# EECS430PhasedArray.net
KiCad netlist of a schematic drawn in Altium Designer
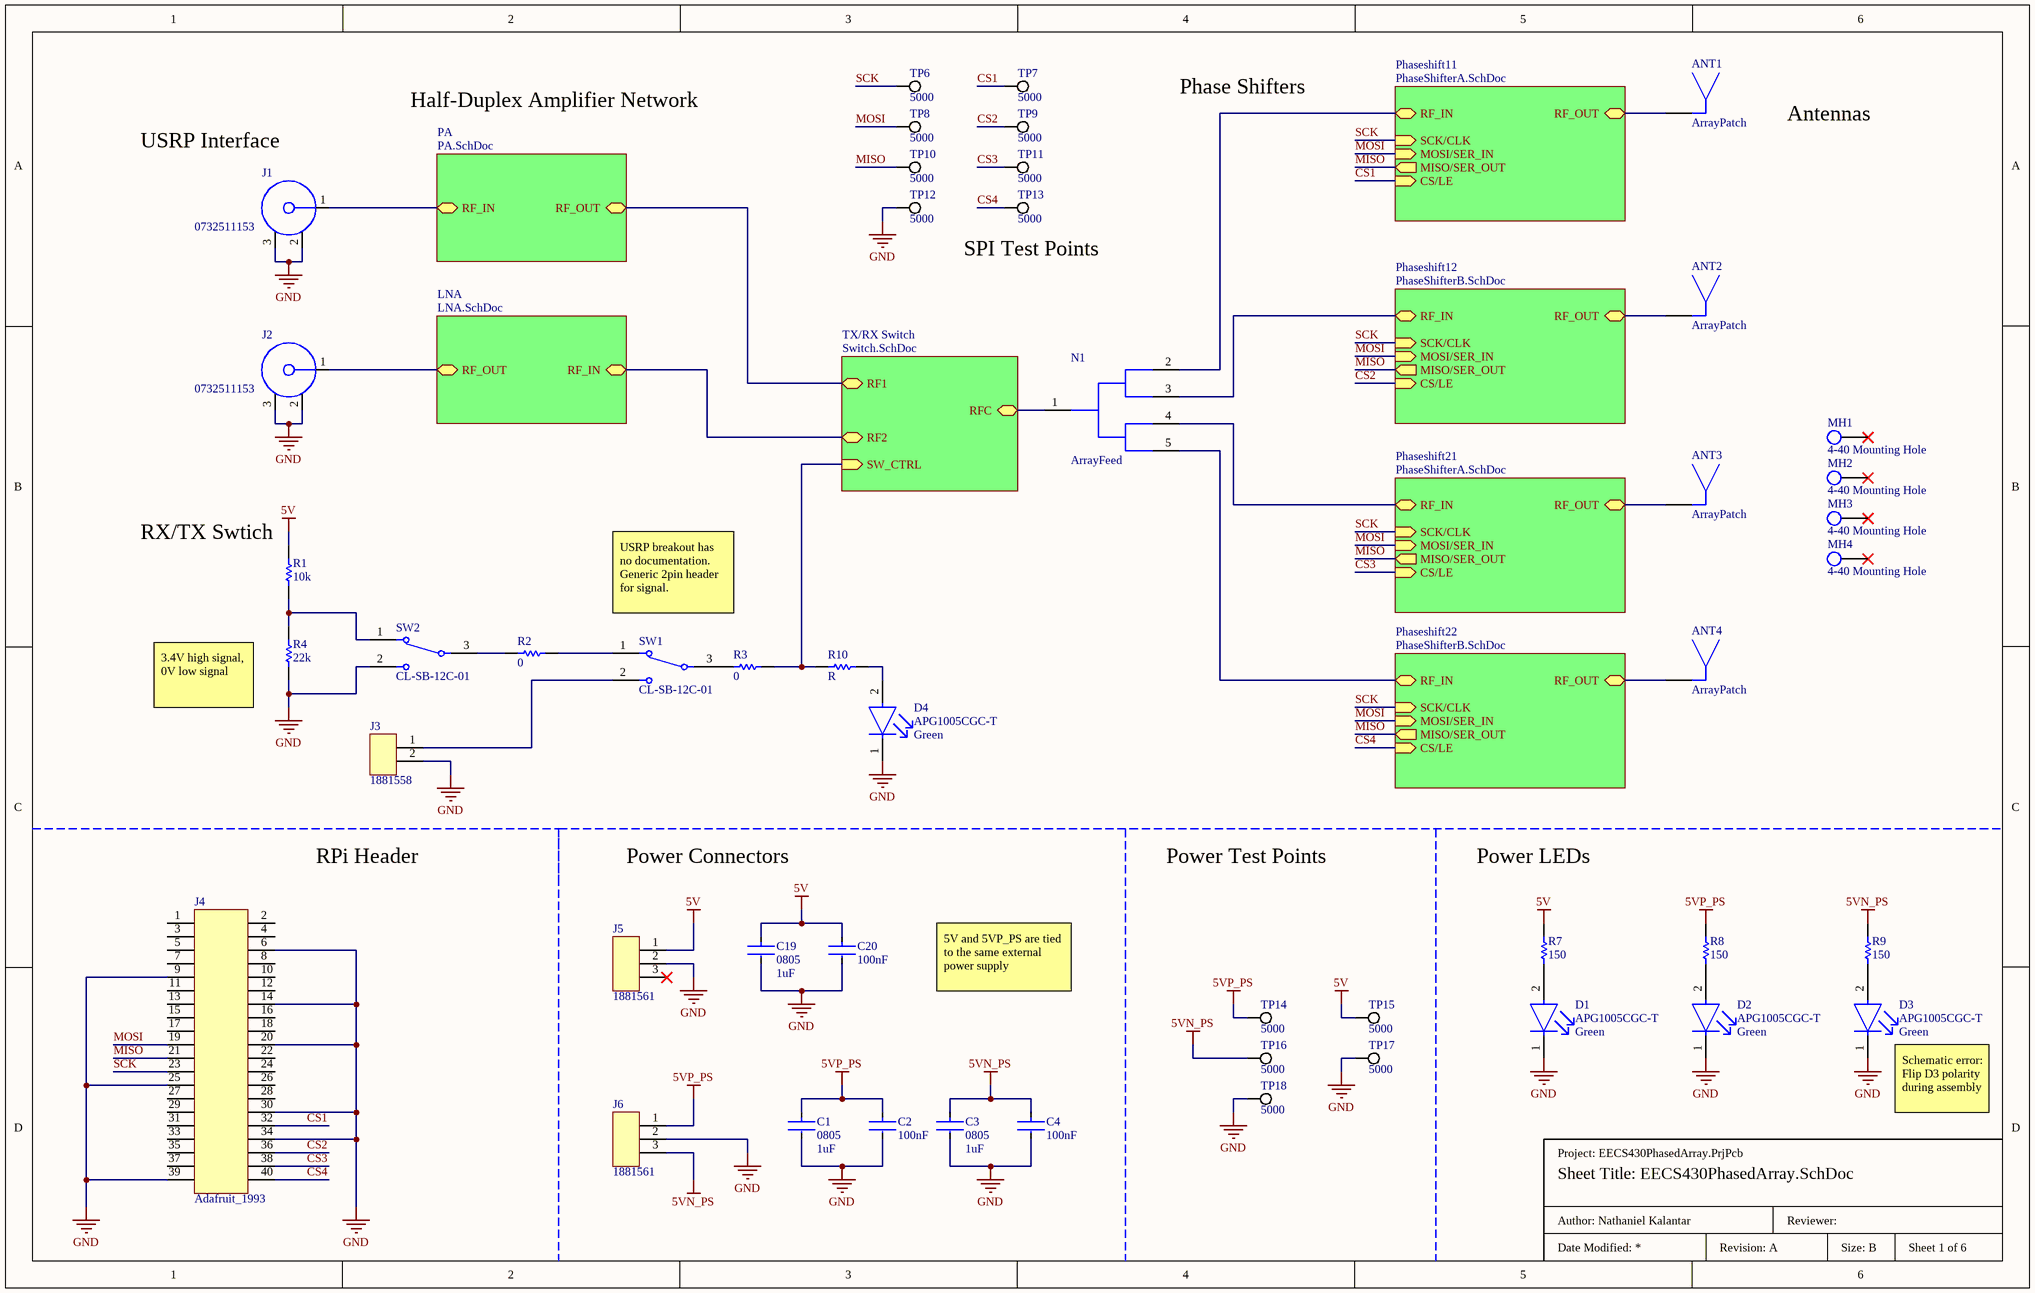
[diagram p0: EECS430PhasedArray.SchDoc]

(export (version "E")
  (design (tool "Eeschema 10.0.6"))
  (components
    (comp (ref "ANT1")
      (value "ArrayPatch")
      (footprint "ArrayPatch")
      (description "Copper footprint for patch antenna element")
      (libsource (lib "EECS430PhasedArray") (part "ArrayPatch"))
    )
    (comp (ref "ANT2")
      (value "ArrayPatch")
      (footprint "ArrayPatch")
      (description "Copper footprint for patch antenna element")
      (libsource (lib "EECS430PhasedArray") (part "ArrayPatch"))
    )
    (comp (ref "ANT3")
      (value "ArrayPatch")
      (footprint "ArrayPatch")
      (description "Copper footprint for patch antenna element")
      (libsource (lib "EECS430PhasedArray") (part "ArrayPatch"))
    )
    (comp (ref "ANT4")
      (value "ArrayPatch")
      (footprint "ArrayPatch")
      (description "Copper footprint for patch antenna element")
      (libsource (lib "EECS430PhasedArray") (part "ArrayPatch"))
    )
    (comp (ref "C1")
      (value "1uF")
      (footprint "FP-0805-Capacitor-CL21-IPC_B")
      (description "CAP CER 50V X7R 0805")
      (fields
        (field (name "TOLERANCE") "0.1")
        (field (name "MANUFACTURER") "KEMET")
        (field (name "PACKAGE") "0805")
      )
      (libsource (lib "EECS430PhasedArray") (part "Ceramic Capacitor 0805"))
    )
    (comp (ref "C2")
      (value "100nF")
      (footprint "FP-0603-Capacitor-CL10-IPC_B")
      (description "CAP CER 50V X7R 0603")
      (fields (field (name "TOLERANCE") "0.1") (field (name "MANUFACTURER") "KEMET"))
      (libsource (lib "EECS430PhasedArray") (part "Ceramic Capacitor 0603"))
    )
    (comp (ref "C3")
      (value "1uF")
      (footprint "FP-0805-Capacitor-CL21-IPC_B")
      (description "CAP CER 50V X7R 0805")
      (fields
        (field (name "TOLERANCE") "0.1")
        (field (name "MANUFACTURER") "KEMET")
        (field (name "PACKAGE") "0805")
      )
      (libsource (lib "EECS430PhasedArray") (part "Ceramic Capacitor 0805"))
    )
    (comp (ref "C4")
      (value "100nF")
      (footprint "FP-0603-Capacitor-CL10-IPC_B")
      (description "CAP CER 50V X7R 0603")
      (fields (field (name "TOLERANCE") "0.1") (field (name "MANUFACTURER") "KEMET"))
      (libsource (lib "EECS430PhasedArray") (part "Ceramic Capacitor 0603"))
    )
    (comp (ref "C19")
      (value "1uF")
      (footprint "FP-0805-Capacitor-CL21-IPC_B")
      (description "CAP CER 50V X7R 0805")
      (fields
        (field (name "TOLERANCE") "0.1")
        (field (name "MANUFACTURER") "KEMET")
        (field (name "PACKAGE") "0805")
      )
      (libsource (lib "EECS430PhasedArray") (part "Ceramic Capacitor 0805"))
    )
    (comp (ref "C20")
      (value "100nF")
      (footprint "FP-0603-Capacitor-CL10-IPC_B")
      (description "CAP CER 50V X7R 0603")
      (fields (field (name "TOLERANCE") "0.1") (field (name "MANUFACTURER") "KEMET"))
      (libsource (lib "EECS430PhasedArray") (part "Ceramic Capacitor 0603"))
    )
    (comp (ref "D1")
      (value "APG1005CGC-T")
      (footprint "FP-APG1005CGC-T-MFG")
      (description "LED GREEN CLEAR CHIP SMD")
      (fields (field (name "COLOR") "Green"))
      (libsource (lib "EECS430PhasedArray") (part "APG1005CGC-T"))
    )
    (comp (ref "D2")
      (value "APG1005CGC-T")
      (footprint "FP-APG1005CGC-T-MFG")
      (description "LED GREEN CLEAR CHIP SMD")
      (fields (field (name "COLOR") "Green"))
      (libsource (lib "EECS430PhasedArray") (part "APG1005CGC-T"))
    )
    (comp (ref "D3")
      (value "APG1005CGC-T")
      (footprint "FP-APG1005CGC-T-MFG")
      (description "LED GREEN CLEAR CHIP SMD")
      (fields (field (name "COLOR") "Green"))
      (libsource (lib "EECS430PhasedArray") (part "APG1005CGC-T"))
    )
    (comp (ref "D4")
      (value "APG1005CGC-T")
      (footprint "FP-APG1005CGC-T-MFG")
      (description "LED GREEN CLEAR CHIP SMD")
      (fields (field (name "COLOR") "Green"))
      (libsource (lib "EECS430PhasedArray") (part "APG1005CGC-T"))
    )
    (comp (ref "J1")
      (value "0732511153")
      (footprint "0732511153")
      (description "SMA Connector Jack, Female Socket 50 Ohms Board Edge, End Launch Solder")
      (libsource (lib "EECS430PhasedArray") (part "0732511153"))
    )
    (comp (ref "J2")
      (value "0732511153")
      (footprint "0732511153")
      (description "SMA Connector Jack, Female Socket 50 Ohms Board Edge, End Launch Solder")
      (libsource (lib "EECS430PhasedArray") (part "0732511153"))
    )
    (comp (ref "J3")
      (value "1881558")
      (footprint "1881558")
      (libsource (lib "EECS430PhasedArray") (part "1881558"))
    )
    (comp (ref "J4")
      (value "Adafruit_1993")
      (footprint "Aadafruit_1993")
      (description "2x20 pin Male IDC Box Header - Raspberry Pi A+/B+/Pi 2/Pi 3/Pi 4")
      (libsource (lib "EECS430PhasedArray") (part "Adafruit_1993"))
    )
    (comp (ref "J5")
      (value "1881561")
      (footprint "1881561")
      (libsource (lib "EECS430PhasedArray") (part "1881561"))
    )
    (comp (ref "J6")
      (value "1881561")
      (footprint "1881561")
      (libsource (lib "EECS430PhasedArray") (part "1881561"))
    )
    (comp (ref "MH1")
      (value "4-40 Mounting Hole")
      (footprint "4-40 Mounting Hole")
      (libsource (lib "EECS430PhasedArray") (part "4-40 Mounting Hole"))
    )
    (comp (ref "MH2")
      (value "4-40 Mounting Hole")
      (footprint "4-40 Mounting Hole")
      (libsource (lib "EECS430PhasedArray") (part "4-40 Mounting Hole"))
    )
    (comp (ref "MH3")
      (value "4-40 Mounting Hole")
      (footprint "4-40 Mounting Hole")
      (libsource (lib "EECS430PhasedArray") (part "4-40 Mounting Hole"))
    )
    (comp (ref "MH4")
      (value "4-40 Mounting Hole")
      (footprint "4-40 Mounting Hole")
      (libsource (lib "EECS430PhasedArray") (part "4-40 Mounting Hole"))
    )
    (comp (ref "N1")
      (value "ArrayFeed")
      (footprint "ArrayFeed")
      (description "Copper net tie for 1:4 splitter/combiner")
      (libsource (lib "EECS430PhasedArray") (part "ArrayFeed"))
    )
    (comp (ref "R1")
      (value "10k")
      (footprint "RESC1608X55X25NL10T15")
      (fields
        (field (name "TOLERANCE") "1%")
        (field (name "MANUFACTURER") "Yageo")
        (field (name "Comment") "RC0603FR-072K2L")
      )
      (libsource (lib "EECS430PhasedArray") (part "Resistor 0603"))
    )
    (comp (ref "R2")
      (value "0")
      (footprint "RESC1608X55X25NL10T15")
      (fields
        (field (name "TOLERANCE") "1%")
        (field (name "MANUFACTURER") "Yageo")
        (field (name "Comment") "RC0603FR-072K2L")
      )
      (libsource (lib "EECS430PhasedArray") (part "Resistor 0603"))
    )
    (comp (ref "R3")
      (value "0")
      (footprint "RESC1608X55X25NL10T15")
      (fields
        (field (name "TOLERANCE") "1%")
        (field (name "MANUFACTURER") "Yageo")
        (field (name "Comment") "RC0603FR-072K2L")
      )
      (libsource (lib "EECS430PhasedArray") (part "Resistor 0603"))
    )
    (comp (ref "R4")
      (value "22k")
      (footprint "RESC1608X55X25NL10T15")
      (fields
        (field (name "TOLERANCE") "1%")
        (field (name "MANUFACTURER") "Yageo")
        (field (name "Comment") "RC0603FR-072K2L")
      )
      (libsource (lib "EECS430PhasedArray") (part "Resistor 0603"))
    )
    (comp (ref "R7")
      (value "150")
      (footprint "RESC1608X55X25NL10T15")
      (fields
        (field (name "TOLERANCE") "1%")
        (field (name "MANUFACTURER") "Yageo")
        (field (name "Comment") "RC0603FR-072K2L")
      )
      (libsource (lib "EECS430PhasedArray") (part "Resistor 0603"))
    )
    (comp (ref "R8")
      (value "150")
      (footprint "RESC1608X55X25NL10T15")
      (fields
        (field (name "TOLERANCE") "1%")
        (field (name "MANUFACTURER") "Yageo")
        (field (name "Comment") "RC0603FR-072K2L")
      )
      (libsource (lib "EECS430PhasedArray") (part "Resistor 0603"))
    )
    (comp (ref "R9")
      (value "150")
      (footprint "RESC1608X55X25NL10T15")
      (fields
        (field (name "TOLERANCE") "1%")
        (field (name "MANUFACTURER") "Yageo")
        (field (name "Comment") "RC0603FR-072K2L")
      )
      (libsource (lib "EECS430PhasedArray") (part "Resistor 0603"))
    )
    (comp (ref "R10")
      (value "R")
      (footprint "RESC1608X55X25NL10T15")
      (fields
        (field (name "TOLERANCE") "1%")
        (field (name "MANUFACTURER") "Yageo")
        (field (name "Comment") "RC0603FR-072K2L")
      )
      (libsource (lib "EECS430PhasedArray") (part "Resistor 0603"))
    )
    (comp (ref "SW1")
      (value "CL-SB-12C-01")
      (footprint "CL-SB-12C-01")
      (description "Slide Switch SPDT Through Hole")
      (libsource (lib "EECS430PhasedArray") (part "CL-SB-12C-01"))
    )
    (comp (ref "SW2")
      (value "CL-SB-12C-01")
      (footprint "CL-SB-12C-01")
      (description "Slide Switch SPDT Through Hole")
      (libsource (lib "EECS430PhasedArray") (part "CL-SB-12C-01"))
    )
    (comp (ref "TP6")
      (value "5000")
      (footprint "FP-5000-MFG")
      (description "Red PC Test Point, Miniature Phosphor Bronze Silver Plating Through Hole Mounting Type")
      (libsource (lib "EECS430PhasedArray") (part "5000"))
    )
    (comp (ref "TP7")
      (value "5000")
      (footprint "FP-5000-MFG")
      (description "Red PC Test Point, Miniature Phosphor Bronze Silver Plating Through Hole Mounting Type")
      (libsource (lib "EECS430PhasedArray") (part "5000"))
    )
    (comp (ref "TP8")
      (value "5000")
      (footprint "FP-5000-MFG")
      (description "Red PC Test Point, Miniature Phosphor Bronze Silver Plating Through Hole Mounting Type")
      (libsource (lib "EECS430PhasedArray") (part "5000"))
    )
    (comp (ref "TP9")
      (value "5000")
      (footprint "FP-5000-MFG")
      (description "Red PC Test Point, Miniature Phosphor Bronze Silver Plating Through Hole Mounting Type")
      (libsource (lib "EECS430PhasedArray") (part "5000"))
    )
    (comp (ref "TP10")
      (value "5000")
      (footprint "FP-5000-MFG")
      (description "Red PC Test Point, Miniature Phosphor Bronze Silver Plating Through Hole Mounting Type")
      (libsource (lib "EECS430PhasedArray") (part "5000"))
    )
    (comp (ref "TP11")
      (value "5000")
      (footprint "FP-5000-MFG")
      (description "Red PC Test Point, Miniature Phosphor Bronze Silver Plating Through Hole Mounting Type")
      (libsource (lib "EECS430PhasedArray") (part "5000"))
    )
    (comp (ref "TP12")
      (value "5000")
      (footprint "FP-5000-MFG")
      (description "Red PC Test Point, Miniature Phosphor Bronze Silver Plating Through Hole Mounting Type")
      (libsource (lib "EECS430PhasedArray") (part "5000"))
    )
    (comp (ref "TP13")
      (value "5000")
      (footprint "FP-5000-MFG")
      (description "Red PC Test Point, Miniature Phosphor Bronze Silver Plating Through Hole Mounting Type")
      (libsource (lib "EECS430PhasedArray") (part "5000"))
    )
    (comp (ref "TP14")
      (value "5000")
      (footprint "FP-5000-MFG")
      (description "Red PC Test Point, Miniature Phosphor Bronze Silver Plating Through Hole Mounting Type")
      (libsource (lib "EECS430PhasedArray") (part "5000"))
    )
    (comp (ref "TP15")
      (value "5000")
      (footprint "FP-5000-MFG")
      (description "Red PC Test Point, Miniature Phosphor Bronze Silver Plating Through Hole Mounting Type")
      (libsource (lib "EECS430PhasedArray") (part "5000"))
    )
    (comp (ref "TP16")
      (value "5000")
      (footprint "FP-5000-MFG")
      (description "Red PC Test Point, Miniature Phosphor Bronze Silver Plating Through Hole Mounting Type")
      (libsource (lib "EECS430PhasedArray") (part "5000"))
    )
    (comp (ref "TP17")
      (value "5000")
      (footprint "FP-5000-MFG")
      (description "Red PC Test Point, Miniature Phosphor Bronze Silver Plating Through Hole Mounting Type")
      (libsource (lib "EECS430PhasedArray") (part "5000"))
    )
    (comp (ref "TP18")
      (value "5000")
      (footprint "FP-5000-MFG")
      (description "Red PC Test Point, Miniature Phosphor Bronze Silver Plating Through Hole Mounting Type")
      (libsource (lib "EECS430PhasedArray") (part "5000"))
    )
  )
  (nets
    (net (code "1") (name "/CS1") (class "Default")
      (node (ref "J4") (pin "32") (pintype "passive"))
      (node (ref "TP7") (pin "1") (pinfunction "1_1") (pintype "passive"))
    )
    (net (code "2") (name "/CS2") (class "Default")
      (node (ref "J4") (pin "36") (pintype "passive"))
      (node (ref "TP9") (pin "1") (pinfunction "1_1") (pintype "passive"))
    )
    (net (code "3") (name "/CS3") (class "Default")
      (node (ref "J4") (pin "38") (pintype "passive"))
      (node (ref "TP11") (pin "1") (pinfunction "1_1") (pintype "passive"))
    )
    (net (code "4") (name "/CS4") (class "Default")
      (node (ref "J4") (pin "40") (pintype "passive"))
      (node (ref "TP13") (pin "1") (pinfunction "1_1") (pintype "passive"))
    )
    (net (code "5") (name "/MISO") (class "Default")
      (node (ref "J4") (pin "21") (pintype "passive"))
      (node (ref "TP10") (pin "1") (pinfunction "1_1") (pintype "passive"))
    )
    (net (code "6") (name "/MOSI") (class "Default")
      (node (ref "J4") (pin "19") (pintype "passive"))
      (node (ref "TP8") (pin "1") (pinfunction "1_1") (pintype "passive"))
    )
    (net (code "9") (name "/RFC") (class "Default")
      (node (ref "N1") (pin "1") (pinfunction "RFC_1") (pintype "passive"))
    )
    (net (code "10") (name "/RF_IN") (class "Default")
      (node (ref "N1") (pin "3") (pinfunction "RF2_3") (pintype "passive"))
    )
    (net (code "11") (name "/RF_IN_1") (class "Default") (node (ref "J1") (pin "1") (pintype "passive")))
    (net (code "12") (name "/RF_IN_2") (class "Default")
      (node (ref "N1") (pin "4") (pinfunction "RF3_4") (pintype "passive"))
    )
    (net (code "13") (name "/RF_IN_3") (class "Default")
      (node (ref "N1") (pin "5") (pinfunction "RF4_5") (pintype "passive"))
    )
    (net (code "14") (name "/RF_IN_4") (class "Default")
      (node (ref "N1") (pin "2") (pinfunction "RF1_2") (pintype "passive"))
    )
    (net (code "15") (name "/RF_OUT") (class "Default")
      (node (ref "ANT2") (pin "1") (pinfunction "ANT_1") (pintype "passive"))
    )
    (net (code "16") (name "/RF_OUT_1") (class "Default") (node (ref "J2") (pin "1") (pintype "passive")))
    (net (code "17") (name "/RF_OUT_2") (class "Default")
      (node (ref "ANT4") (pin "1") (pinfunction "ANT_1") (pintype "passive"))
    )
    (net (code "18") (name "/RF_OUT_3") (class "Default")
      (node (ref "ANT3") (pin "1") (pinfunction "ANT_1") (pintype "passive"))
    )
    (net (code "19") (name "/RF_OUT_4") (class "Default")
      (node (ref "ANT1") (pin "1") (pinfunction "ANT_1") (pintype "passive"))
    )
    (net (code "20") (name "/SCK") (class "Default")
      (node (ref "J4") (pin "23") (pintype "passive"))
      (node (ref "TP6") (pin "1") (pinfunction "1_1") (pintype "passive"))
    )
    (net (code "21") (name "/SW_CTRL") (class "Default")
      (node (ref "R10") (pin "2") (pinfunction "2_2") (pintype "passive"))
      (node (ref "R3") (pin "1") (pinfunction "1_1") (pintype "passive"))
    )
    (net (code "22") (name "5V") (class "Default")
      (node (ref "C19") (pin "1") (pinfunction "1_1") (pintype "passive"))
      (node (ref "C20") (pin "1") (pinfunction "1_1") (pintype "passive"))
      (node (ref "J5") (pin "1") (pinfunction "1_1") (pintype "passive"))
      (node (ref "R1") (pin "2") (pinfunction "2_2") (pintype "passive"))
      (node (ref "R7") (pin "2") (pinfunction "2_2") (pintype "passive"))
      (node (ref "TP15") (pin "1") (pinfunction "1_1") (pintype "passive"))
    )
    (net (code "23") (name "5VN_PS") (class "Default")
      (node (ref "C3") (pin "1") (pinfunction "1_1") (pintype "passive"))
      (node (ref "C4") (pin "1") (pinfunction "1_1") (pintype "passive"))
      (node (ref "J6") (pin "3") (pinfunction "3_3") (pintype "passive"))
      (node (ref "R9") (pin "1") (pinfunction "1_1") (pintype "passive"))
      (node (ref "TP16") (pin "1") (pinfunction "1_1") (pintype "passive"))
    )
    (net (code "24") (name "5VP_PS") (class "Default")
      (node (ref "C1") (pin "1") (pinfunction "1_1") (pintype "passive"))
      (node (ref "C2") (pin "1") (pinfunction "1_1") (pintype "passive"))
      (node (ref "J6") (pin "1") (pinfunction "1_1") (pintype "passive"))
      (node (ref "R8") (pin "2") (pinfunction "2_2") (pintype "passive"))
      (node (ref "TP14") (pin "1") (pinfunction "1_1") (pintype "passive"))
    )
    (net (code "25") (name "GND") (class "Default")
      (node (ref "C1") (pin "2") (pinfunction "2_2") (pintype "passive"))
      (node (ref "C19") (pin "2") (pinfunction "2_2") (pintype "passive"))
      (node (ref "C2") (pin "2") (pinfunction "2_2") (pintype "passive"))
      (node (ref "C20") (pin "2") (pinfunction "2_2") (pintype "passive"))
      (node (ref "C3") (pin "2") (pinfunction "2_2") (pintype "passive"))
      (node (ref "C4") (pin "2") (pinfunction "2_2") (pintype "passive"))
      (node (ref "D1") (pin "1") (pinfunction "C_1") (pintype "passive"))
      (node (ref "D2") (pin "1") (pinfunction "C_1") (pintype "passive"))
      (node (ref "D3") (pin "1") (pinfunction "C_1") (pintype "passive"))
      (node (ref "D4") (pin "1") (pinfunction "C_1") (pintype "passive"))
      (node (ref "J1") (pin "2") (pintype "passive"))
      (node (ref "J1") (pin "3") (pintype "passive"))
      (node (ref "J2") (pin "2") (pintype "passive"))
      (node (ref "J2") (pin "3") (pintype "passive"))
      (node (ref "J3") (pin "2") (pinfunction "2_2") (pintype "passive"))
      (node (ref "J4") (pin "14") (pintype "passive"))
      (node (ref "J4") (pin "20") (pintype "passive"))
      (node (ref "J4") (pin "25") (pintype "passive"))
      (node (ref "J4") (pin "30") (pintype "passive"))
      (node (ref "J4") (pin "34") (pintype "passive"))
      (node (ref "J4") (pin "39") (pintype "passive"))
      (node (ref "J4") (pin "6") (pintype "passive"))
      (node (ref "J4") (pin "9") (pintype "passive"))
      (node (ref "J5") (pin "2") (pinfunction "2_2") (pintype "passive"))
      (node (ref "J6") (pin "2") (pinfunction "2_2") (pintype "passive"))
      (node (ref "R4") (pin "1") (pinfunction "1_1") (pintype "passive"))
      (node (ref "SW2") (pin "2") (pinfunction "2_2") (pintype "passive"))
      (node (ref "TP12") (pin "1") (pinfunction "1_1") (pintype "passive"))
      (node (ref "TP17") (pin "1") (pinfunction "1_1") (pintype "passive"))
      (node (ref "TP18") (pin "1") (pinfunction "1_1") (pintype "passive"))
    )
    (net (code "26") (name "Net-(D1-A)") (class "Default")
      (node (ref "D1") (pin "2") (pinfunction "A_2") (pintype "passive"))
      (node (ref "R7") (pin "1") (pinfunction "1_1") (pintype "passive"))
    )
    (net (code "27") (name "Net-(D2-A)") (class "Default")
      (node (ref "D2") (pin "2") (pinfunction "A_2") (pintype "passive"))
      (node (ref "R8") (pin "1") (pinfunction "1_1") (pintype "passive"))
    )
    (net (code "28") (name "Net-(D3-A)") (class "Default")
      (node (ref "D3") (pin "2") (pinfunction "A_2") (pintype "passive"))
      (node (ref "R9") (pin "2") (pinfunction "2_2") (pintype "passive"))
    )
    (net (code "29") (name "Net-(D4-A)") (class "Default")
      (node (ref "D4") (pin "2") (pinfunction "A_2") (pintype "passive"))
      (node (ref "R10") (pin "1") (pinfunction "1_1") (pintype "passive"))
    )
    (net (code "30") (name "Net-(J3-Pad1)") (class "Default")
      (node (ref "J3") (pin "1") (pinfunction "1_1") (pintype "passive"))
      (node (ref "SW1") (pin "2") (pinfunction "2_2") (pintype "passive"))
    )
    (net (code "31") (name "Net-(R1-Pad1)") (class "Default")
      (node (ref "R1") (pin "1") (pinfunction "1_1") (pintype "passive"))
      (node (ref "R4") (pin "2") (pinfunction "2_2") (pintype "passive"))
      (node (ref "SW2") (pin "1") (pinfunction "1_1") (pintype "passive"))
    )
    (net (code "32") (name "Net-(R2-Pad1)") (class "Default")
      (node (ref "R2") (pin "1") (pinfunction "1_1") (pintype "passive"))
      (node (ref "SW1") (pin "1") (pinfunction "1_1") (pintype "passive"))
    )
    (net (code "33") (name "Net-(R2-Pad2)") (class "Default")
      (node (ref "R2") (pin "2") (pinfunction "2_2") (pintype "passive"))
      (node (ref "SW2") (pin "3") (pinfunction "3_3") (pintype "passive"))
    )
    (net (code "34") (name "Net-(R3-Pad2)") (class "Default")
      (node (ref "R3") (pin "2") (pinfunction "2_2") (pintype "passive"))
      (node (ref "SW1") (pin "3") (pinfunction "3_3") (pintype "passive"))
    )
    (net (code "35") (name "unconnected-(J4-Pad1)") (class "Default")
      (node (ref "J4") (pin "1") (pintype "passive"))
    )
    (net (code "36") (name "unconnected-(J4-Pad2)") (class "Default")
      (node (ref "J4") (pin "2") (pintype "passive"))
    )
    (net (code "37") (name "unconnected-(J4-Pad3)") (class "Default")
      (node (ref "J4") (pin "3") (pintype "passive"))
    )
    (net (code "38") (name "unconnected-(J4-Pad4)") (class "Default")
      (node (ref "J4") (pin "4") (pintype "passive"))
    )
    (net (code "39") (name "unconnected-(J4-Pad5)") (class "Default")
      (node (ref "J4") (pin "5") (pintype "passive"))
    )
    (net (code "40") (name "unconnected-(J4-Pad7)") (class "Default")
      (node (ref "J4") (pin "7") (pintype "passive"))
    )
    (net (code "41") (name "unconnected-(J4-Pad8)") (class "Default")
      (node (ref "J4") (pin "8") (pintype "passive"))
    )
    (net (code "42") (name "unconnected-(J4-Pad10)") (class "Default")
      (node (ref "J4") (pin "10") (pintype "passive"))
    )
    (net (code "43") (name "unconnected-(J4-Pad11)") (class "Default")
      (node (ref "J4") (pin "11") (pintype "passive"))
    )
    (net (code "44") (name "unconnected-(J4-Pad12)") (class "Default")
      (node (ref "J4") (pin "12") (pintype "passive"))
    )
    (net (code "45") (name "unconnected-(J4-Pad13)") (class "Default")
      (node (ref "J4") (pin "13") (pintype "passive"))
    )
    (net (code "46") (name "unconnected-(J4-Pad15)") (class "Default")
      (node (ref "J4") (pin "15") (pintype "passive"))
    )
    (net (code "47") (name "unconnected-(J4-Pad16)") (class "Default")
      (node (ref "J4") (pin "16") (pintype "passive"))
    )
    (net (code "48") (name "unconnected-(J4-Pad17)") (class "Default")
      (node (ref "J4") (pin "17") (pintype "passive"))
    )
    (net (code "49") (name "unconnected-(J4-Pad18)") (class "Default")
      (node (ref "J4") (pin "18") (pintype "passive"))
    )
    (net (code "50") (name "unconnected-(J4-Pad22)") (class "Default")
      (node (ref "J4") (pin "22") (pintype "passive"))
    )
    (net (code "51") (name "unconnected-(J4-Pad24)") (class "Default")
      (node (ref "J4") (pin "24") (pintype "passive"))
    )
    (net (code "52") (name "unconnected-(J4-Pad26)") (class "Default")
      (node (ref "J4") (pin "26") (pintype "passive"))
    )
    (net (code "53") (name "unconnected-(J4-Pad27)") (class "Default")
      (node (ref "J4") (pin "27") (pintype "passive"))
    )
    (net (code "54") (name "unconnected-(J4-Pad28)") (class "Default")
      (node (ref "J4") (pin "28") (pintype "passive"))
    )
    (net (code "55") (name "unconnected-(J4-Pad29)") (class "Default")
      (node (ref "J4") (pin "29") (pintype "passive"))
    )
    (net (code "56") (name "unconnected-(J4-Pad31)") (class "Default")
      (node (ref "J4") (pin "31") (pintype "passive"))
    )
    (net (code "57") (name "unconnected-(J4-Pad33)") (class "Default")
      (node (ref "J4") (pin "33") (pintype "passive"))
    )
    (net (code "58") (name "unconnected-(J4-Pad35)") (class "Default")
      (node (ref "J4") (pin "35") (pintype "passive"))
    )
    (net (code "59") (name "unconnected-(J4-Pad37)") (class "Default")
      (node (ref "J4") (pin "37") (pintype "passive"))
    )
    (net (code "60") (name "unconnected-(J5-Pad3)") (class "Default")
      (node (ref "J5") (pin "3") (pinfunction "3_3") (pintype "passive+no_connect"))
    )
    (net (code "61") (name "unconnected-(MH1-Pad1)") (class "Default")
      (node (ref "MH1") (pin "1") (pintype "passive+no_connect"))
    )
    (net (code "62") (name "unconnected-(MH2-Pad1)") (class "Default")
      (node (ref "MH2") (pin "1") (pintype "passive+no_connect"))
    )
    (net (code "63") (name "unconnected-(MH3-Pad1)") (class "Default")
      (node (ref "MH3") (pin "1") (pintype "passive+no_connect"))
    )
    (net (code "64") (name "unconnected-(MH4-Pad1)") (class "Default")
      (node (ref "MH4") (pin "1") (pintype "passive+no_connect"))
    )
  )
)
